# BandpassFilter_v1.net
KiCad netlist of a schematic drawn in Altium Designer
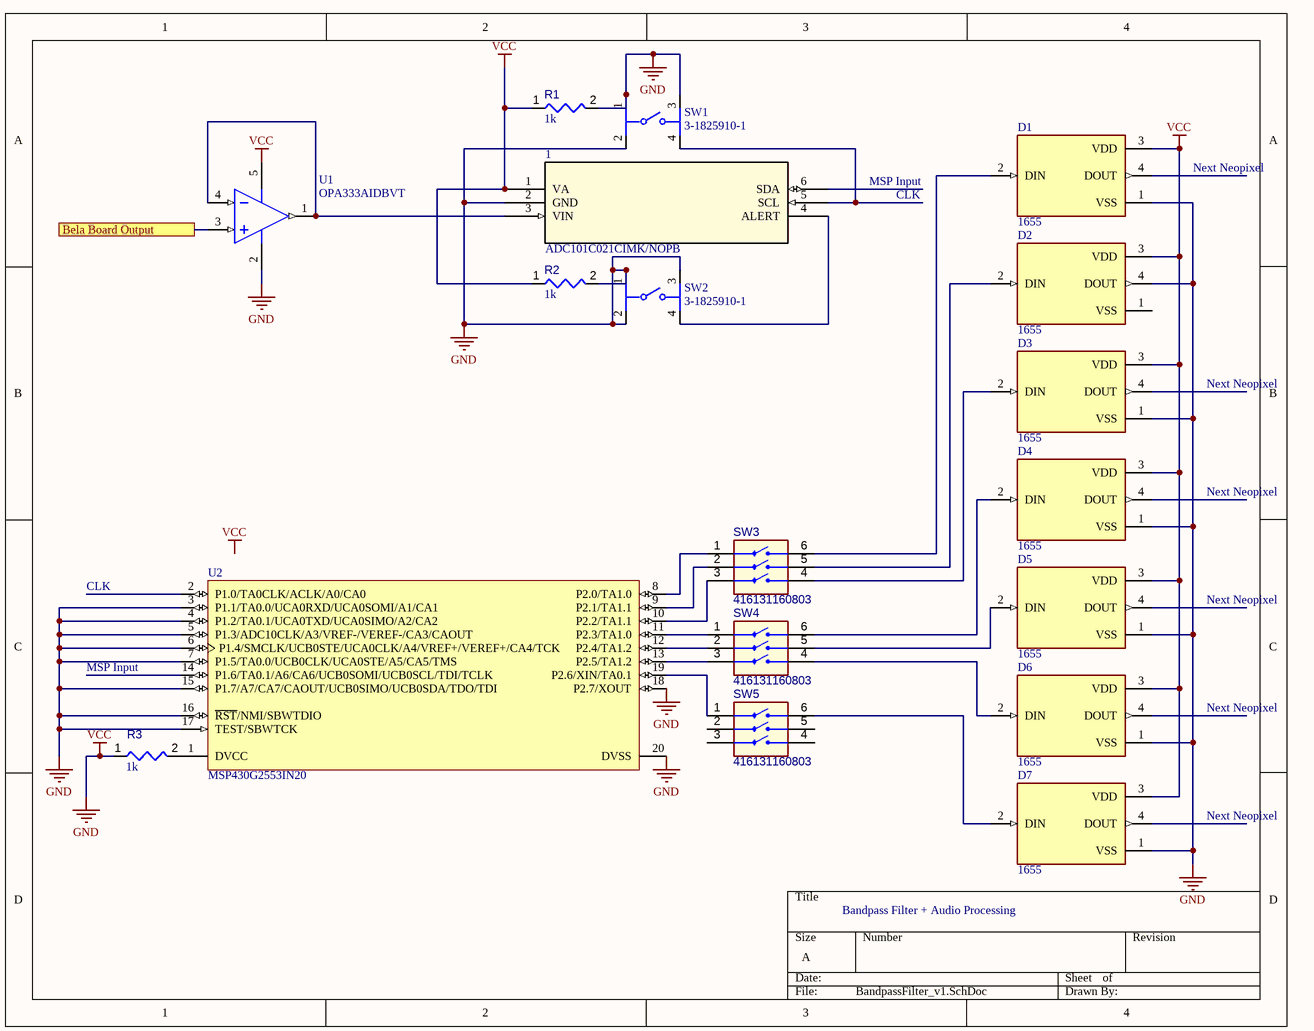
[diagram p0: BandpassFilter_v1.SchDoc]

(export (version "E")
  (design (tool "Eeschema 10.0.6"))
  (components
    (comp (ref "1")
      (value "ADC101C021CIMK/NOPB")
      (footprint "MK06A")
      (description "No Description Available")
      (fields (field (name "COPYRIGHT") "Copyright (C) 2022 Ultra Librarian. All rights reserved."))
      (libsource (lib "ADC101C021CIMK&slash_NOPB") (part "ADC101C021CIMK/NOPB"))
    )
    (comp (ref "D1")
      (value "1655")
      (footprint "SnapEDApcb:LED_1655")
      (fields (field (name "MF") "Adafruit Industries"))
      (libsource (lib "SnapEDAsch") (part "1655"))
    )
    (comp (ref "D2")
      (value "1655")
      (footprint "SnapEDApcb:LED_1655")
      (fields (field (name "MF") "Adafruit Industries"))
      (libsource (lib "SnapEDAsch") (part "1655"))
    )
    (comp (ref "D3")
      (value "1655")
      (footprint "SnapEDApcb:LED_1655")
      (fields (field (name "MF") "Adafruit Industries"))
      (libsource (lib "SnapEDAsch") (part "1655"))
    )
    (comp (ref "D4")
      (value "1655")
      (footprint "SnapEDApcb:LED_1655")
      (fields (field (name "MF") "Adafruit Industries"))
      (libsource (lib "SnapEDAsch") (part "1655"))
    )
    (comp (ref "D5")
      (value "1655")
      (footprint "SnapEDApcb:LED_1655")
      (fields (field (name "MF") "Adafruit Industries"))
      (libsource (lib "SnapEDAsch") (part "1655"))
    )
    (comp (ref "D6")
      (value "1655")
      (footprint "SnapEDApcb:LED_1655")
      (fields (field (name "MF") "Adafruit Industries"))
      (libsource (lib "SnapEDAsch") (part "1655"))
    )
    (comp (ref "D7")
      (value "1655")
      (footprint "SnapEDApcb:LED_1655")
      (fields (field (name "MF") "Adafruit Industries"))
      (libsource (lib "SnapEDAsch") (part "1655"))
    )
    (comp (ref "R1")
      (value "1k")
      (footprint "RESC0402(1005)_L")
      (description "Chip Resistor, 2,2 Ohms, +/-5 %, 63 mW, -55 to 155 degC, 0402")
      (fields (field (name "POWER") "63mW") (field (name "TOLERANCE") "5%"))
      (libsource (lib "University of California, Davis") (part "RES-2"))
    )
    (comp (ref "R2")
      (value "1k")
      (footprint "RESC0402(1005)_L")
      (description "Chip Resistor, 2,2 Ohms, +/-5 %, 63 mW, -55 to 155 degC, 0402")
      (fields (field (name "POWER") "63mW") (field (name "TOLERANCE") "5%"))
      (libsource (lib "University of California, Davis") (part "RES-2"))
    )
    (comp (ref "R3")
      (value "1k")
      (footprint "RESC0402(1005)_L")
      (description "Chip Resistor, 2,2 Ohms, +/-5 %, 63 mW, -55 to 155 degC, 0402")
      (fields (field (name "POWER") "63mW") (field (name "TOLERANCE") "5%"))
      (libsource (lib "University of California, Davis") (part "RES-2"))
    )
    (comp (ref "SW1")
      (value "3-1825910-1")
      (footprint "FP-3-1825910-1-MFG")
      (description "Switch Tactile OFF (ON) SPST Round Button PC Pins 0.05A 24VDC 100000Cycles 1.57N Thru-Hole")
      (fields (field (name "MANUFACTURER") "TE Connectivity"))
      (libsource (lib "Altium Content Vault") (part "b8895f3f4cefb76e1819d2863dba89b"))
    )
    (comp (ref "SW2")
      (value "3-1825910-1")
      (footprint "FP-3-1825910-1-MFG")
      (description "Switch Tactile OFF (ON) SPST Round Button PC Pins 0.05A 24VDC 100000Cycles 1.57N Thru-Hole")
      (fields (field (name "MANUFACTURER") "TE Connectivity"))
      (libsource (lib "Altium Content Vault") (part "b8895f3f4cefb76e1819d2863dba89b"))
    )
    (comp (ref "SW3")
      (value "416131160803")
      (footprint "416131160803")
      (description "WS-DISV 1.27 mm small compact SMD Dip Switch with top tape")
      (libsource (lib "University of California, Davis") (part "CMP-00567-2"))
    )
    (comp (ref "SW4")
      (value "416131160803")
      (footprint "416131160803")
      (description "WS-DISV 1.27 mm small compact SMD Dip Switch with top tape")
      (libsource (lib "University of California, Davis") (part "CMP-00567-2"))
    )
    (comp (ref "SW5")
      (value "416131160803")
      (footprint "416131160803")
      (description "WS-DISV 1.27 mm small compact SMD Dip Switch with top tape")
      (libsource (lib "University of California, Davis") (part "CMP-00567-2"))
    )
    (comp (ref "U1")
      (value "OPA333AIDBVT")
      (footprint "DBV0005A_M")
      (fields (field (name "MANUFACTURER") "Texas Instruments (TI)"))
      (libsource (lib "University of California, Davis") (part "TI-OPA333DBV5"))
    )
    (comp (ref "U2")
      (value "MSP430G2553IN20")
      (footprint "N0020A")
      (fields (field (name "MANUFACTURER") "Texas Instruments"))
      (libsource (lib "EE_Emerge_SkillsProject") (part "CMP-0365-00184-2"))
    )
  )
  (nets
    (net (code "1") (name "/Bela Board Output") (class "Default")
      (node (ref "U1") (pin "3") (pinfunction "+IN_3") (pintype "input"))
    )
    (net (code "2") (name "GND") (class "Default")
      (node (ref "1") (pin "1") (pinfunction "VA_1") (pintype "power_in"))
      (node (ref "1") (pin "2") (pinfunction "GND_2") (pintype "power_in"))
      (node (ref "D1") (pin "1") (pinfunction "VSS_1") (pintype "power_in"))
      (node (ref "D1") (pin "3") (pinfunction "VDD_3") (pintype "power_in"))
      (node (ref "D2") (pin "3") (pinfunction "VDD_3") (pintype "power_in"))
      (node (ref "D2") (pin "4") (pinfunction "DOUT_4") (pintype "output"))
      (node (ref "D3") (pin "1") (pinfunction "VSS_1") (pintype "power_in"))
      (node (ref "D3") (pin "3") (pinfunction "VDD_3") (pintype "power_in"))
      (node (ref "D4") (pin "1") (pinfunction "VSS_1") (pintype "power_in"))
      (node (ref "D4") (pin "3") (pinfunction "VDD_3") (pintype "power_in"))
      (node (ref "D5") (pin "1") (pinfunction "VSS_1") (pintype "power_in"))
      (node (ref "D5") (pin "3") (pinfunction "VDD_3") (pintype "power_in"))
      (node (ref "D6") (pin "1") (pinfunction "VSS_1") (pintype "power_in"))
      (node (ref "D6") (pin "3") (pinfunction "VDD_3") (pintype "power_in"))
      (node (ref "D7") (pin "1") (pinfunction "VSS_1") (pintype "power_in"))
      (node (ref "D7") (pin "3") (pinfunction "VDD_3") (pintype "power_in"))
      (node (ref "R1") (pin "1") (pinfunction "1_1") (pintype "passive"))
      (node (ref "R1") (pin "2") (pinfunction "2_2") (pintype "passive"))
      (node (ref "R2") (pin "1") (pinfunction "1_1") (pintype "passive"))
      (node (ref "R2") (pin "2") (pinfunction "2_2") (pintype "passive"))
      (node (ref "R3") (pin "1") (pinfunction "1_1") (pintype "passive"))
      (node (ref "SW1") (pin "1") (pinfunction "1_1") (pintype "passive"))
      (node (ref "SW1") (pin "2") (pinfunction "2_2") (pintype "passive"))
      (node (ref "SW1") (pin "3") (pinfunction "3_3") (pintype "passive"))
      (node (ref "SW2") (pin "1") (pinfunction "1_1") (pintype "passive"))
      (node (ref "SW2") (pin "2") (pinfunction "2_2") (pintype "passive"))
      (node (ref "SW2") (pin "3") (pinfunction "3_3") (pintype "passive"))
      (node (ref "U1") (pin "2") (pinfunction "V-_2") (pintype "power_in"))
      (node (ref "U1") (pin "5") (pinfunction "V+_5") (pintype "power_in"))
      (node (ref "U2") (pin "15") (pinfunction "P1.7/A7/CA7/CAOUT/UCB0SIMO/UCB0SDA/TDO/TDI_15") (pintype "bidirectional"))
      (node (ref "U2") (pin "16") (pinfunction "~{RST}/NMI/SBWTDIO_16") (pintype "bidirectional"))
      (node (ref "U2") (pin "17") (pinfunction "TEST/SBWTCK_17") (pintype "input"))
      (node (ref "U2") (pin "18") (pinfunction "P2.7/XOUT_18") (pintype "bidirectional"))
      (node (ref "U2") (pin "20") (pinfunction "DVSS_20") (pintype "power_in"))
      (node (ref "U2") (pin "3") (pinfunction "P1.1/TA0.0/UCA0RXD/UCA0SOMI/A1/CA1_3") (pintype "bidirectional"))
      (node (ref "U2") (pin "4") (pinfunction "P1.2/TA0.1/UCA0TXD/UCA0SIMO/A2/CA2_4") (pintype "bidirectional"))
      (node (ref "U2") (pin "5") (pinfunction "P1.3/ADC10CLK/A3/VREF-/VEREF-/CA3/CAOUT_5") (pintype "bidirectional"))
      (node (ref "U2") (pin "6") (pinfunction "P1.4/SMCLK/UCB0STE/UCA0CLK/A4/VREF+/VEREF+/CA4/TCK_6") (pintype "bidirectional"))
      (node (ref "U2") (pin "7") (pinfunction "P1.5/TA0.0/UCB0CLK/UCA0STE/A5/CA5/TMS_7") (pintype "bidirectional"))
    )
    (net (code "3") (name "Net-(1-ALERT)") (class "Default")
      (node (ref "1") (pin "4") (pinfunction "ALERT_4") (pintype "passive"))
      (node (ref "SW2") (pin "4") (pinfunction "4_4") (pintype "passive"))
    )
    (net (code "4") (name "Net-(1-SCL)") (class "Default")
      (node (ref "1") (pin "5") (pinfunction "SCL_5") (pintype "input"))
      (node (ref "SW1") (pin "4") (pinfunction "4_4") (pintype "passive"))
    )
    (net (code "5") (name "Net-(1-VIN)") (class "Default")
      (node (ref "1") (pin "3") (pinfunction "VIN_3") (pintype "input"))
      (node (ref "U1") (pin "1") (pinfunction "OUT_1") (pintype "output"))
      (node (ref "U1") (pin "4") (pinfunction "-IN_4") (pintype "input"))
    )
    (net (code "6") (name "Net-(D1-DIN)") (class "Default")
      (node (ref "D1") (pin "2") (pinfunction "DIN_2") (pintype "input"))
      (node (ref "SW3") (pin "6") (pinfunction "6_6") (pintype "passive"))
    )
    (net (code "7") (name "Net-(D2-DIN)") (class "Default")
      (node (ref "D2") (pin "2") (pinfunction "DIN_2") (pintype "input"))
      (node (ref "SW3") (pin "5") (pinfunction "5_5") (pintype "passive"))
    )
    (net (code "8") (name "Net-(D3-DIN)") (class "Default")
      (node (ref "D3") (pin "2") (pinfunction "DIN_2") (pintype "input"))
      (node (ref "SW3") (pin "4") (pinfunction "4_4") (pintype "passive"))
    )
    (net (code "9") (name "Net-(D4-DIN)") (class "Default")
      (node (ref "D4") (pin "2") (pinfunction "DIN_2") (pintype "input"))
      (node (ref "SW4") (pin "6") (pinfunction "6_6") (pintype "passive"))
    )
    (net (code "10") (name "Net-(D5-DIN)") (class "Default")
      (node (ref "D5") (pin "2") (pinfunction "DIN_2") (pintype "input"))
      (node (ref "SW4") (pin "5") (pinfunction "5_5") (pintype "passive"))
    )
    (net (code "11") (name "Net-(D6-DIN)") (class "Default")
      (node (ref "D6") (pin "2") (pinfunction "DIN_2") (pintype "input"))
      (node (ref "SW4") (pin "4") (pinfunction "4_4") (pintype "passive"))
    )
    (net (code "12") (name "Net-(D7-DIN)") (class "Default")
      (node (ref "D7") (pin "2") (pinfunction "DIN_2") (pintype "input"))
      (node (ref "SW5") (pin "6") (pinfunction "6_6") (pintype "passive"))
    )
    (net (code "13") (name "Net-(U2-DVCC)") (class "Default")
      (node (ref "R3") (pin "2") (pinfunction "2_2") (pintype "passive"))
      (node (ref "U2") (pin "1") (pinfunction "DVCC_1") (pintype "power_in"))
    )
    (net (code "14") (name "Net-(U2-P2.0{slash}TA1.0)") (class "Default")
      (node (ref "SW3") (pin "1") (pinfunction "1_1") (pintype "passive"))
      (node (ref "U2") (pin "8") (pinfunction "P2.0/TA1.0_8") (pintype "bidirectional"))
    )
    (net (code "15") (name "Net-(U2-P2.1{slash}TA1.1)") (class "Default")
      (node (ref "SW3") (pin "2") (pinfunction "2_2") (pintype "passive"))
      (node (ref "U2") (pin "9") (pinfunction "P2.1/TA1.1_9") (pintype "bidirectional"))
    )
    (net (code "16") (name "Net-(U2-P2.2{slash}TA1.1)") (class "Default")
      (node (ref "SW3") (pin "3") (pinfunction "3_3") (pintype "passive"))
      (node (ref "U2") (pin "10") (pinfunction "P2.2/TA1.1_10") (pintype "bidirectional"))
    )
    (net (code "17") (name "Net-(U2-P2.3{slash}TA1.0)") (class "Default")
      (node (ref "SW4") (pin "1") (pinfunction "1_1") (pintype "passive"))
      (node (ref "U2") (pin "11") (pinfunction "P2.3/TA1.0_11") (pintype "bidirectional"))
    )
    (net (code "18") (name "Net-(U2-P2.4{slash}TA1.2)") (class "Default")
      (node (ref "SW4") (pin "2") (pinfunction "2_2") (pintype "passive"))
      (node (ref "U2") (pin "12") (pinfunction "P2.4/TA1.2_12") (pintype "bidirectional"))
    )
    (net (code "19") (name "Net-(U2-P2.5{slash}TA1.2)") (class "Default")
      (node (ref "SW4") (pin "3") (pinfunction "3_3") (pintype "passive"))
      (node (ref "U2") (pin "13") (pinfunction "P2.5/TA1.2_13") (pintype "bidirectional"))
    )
    (net (code "20") (name "Net-(U2-P2.6{slash}XIN{slash}TA0.1)") (class "Default")
      (node (ref "SW5") (pin "1") (pinfunction "1_1") (pintype "passive"))
      (node (ref "U2") (pin "19") (pinfunction "P2.6/XIN/TA0.1_19") (pintype "bidirectional"))
    )
    (net (code "21") (name "unconnected-(1-SDA-Pad6)") (class "Default")
      (node (ref "1") (pin "6") (pinfunction "SDA_6") (pintype "bidirectional"))
    )
    (net (code "22") (name "unconnected-(D1-DOUT-Pad4)") (class "Default")
      (node (ref "D1") (pin "4") (pinfunction "DOUT_4") (pintype "output"))
    )
    (net (code "23") (name "unconnected-(D2-VSS-Pad1)") (class "Default")
      (node (ref "D2") (pin "1") (pinfunction "VSS_1") (pintype "power_in"))
    )
    (net (code "24") (name "unconnected-(D3-DOUT-Pad4)") (class "Default")
      (node (ref "D3") (pin "4") (pinfunction "DOUT_4") (pintype "output"))
    )
    (net (code "25") (name "unconnected-(D4-DOUT-Pad4)") (class "Default")
      (node (ref "D4") (pin "4") (pinfunction "DOUT_4") (pintype "output"))
    )
    (net (code "26") (name "unconnected-(D5-DOUT-Pad4)") (class "Default")
      (node (ref "D5") (pin "4") (pinfunction "DOUT_4") (pintype "output"))
    )
    (net (code "27") (name "unconnected-(D6-DOUT-Pad4)") (class "Default")
      (node (ref "D6") (pin "4") (pinfunction "DOUT_4") (pintype "output"))
    )
    (net (code "28") (name "unconnected-(D7-DOUT-Pad4)") (class "Default")
      (node (ref "D7") (pin "4") (pinfunction "DOUT_4") (pintype "output"))
    )
    (net (code "29") (name "unconnected-(SW5-Pad2)") (class "Default")
      (node (ref "SW5") (pin "2") (pinfunction "2_2") (pintype "passive"))
    )
    (net (code "30") (name "unconnected-(SW5-Pad3)") (class "Default")
      (node (ref "SW5") (pin "3") (pinfunction "3_3") (pintype "passive"))
    )
    (net (code "31") (name "unconnected-(SW5-Pad4)") (class "Default")
      (node (ref "SW5") (pin "4") (pinfunction "4_4") (pintype "passive"))
    )
    (net (code "32") (name "unconnected-(SW5-Pad5)") (class "Default")
      (node (ref "SW5") (pin "5") (pinfunction "5_5") (pintype "passive"))
    )
    (net (code "33") (name "unconnected-(U2-P1.0{slash}TA0CLK{slash}ACLK{slash}A0{slash}CA0-Pad2)") (class "Default")
      (node (ref "U2") (pin "2") (pinfunction "P1.0/TA0CLK/ACLK/A0/CA0_2") (pintype "bidirectional"))
    )
    (net (code "34") (name "unconnected-(U2-P1.6{slash}TA0.1{slash}A6{slash}CA6{slash}UCB0SOMI{slash}UCB0SCL{slash}TDI{slash}TCLK-Pad14)") (class "Default")
      (node (ref "U2") (pin "14") (pinfunction "P1.6/TA0.1/A6/CA6/UCB0SOMI/UCB0SCL/TDI/TCLK_14") (pintype "bidirectional"))
    )
  )
)
